# Sheet_V3.net
KiCad netlist of a schematic drawn in Altium Designer
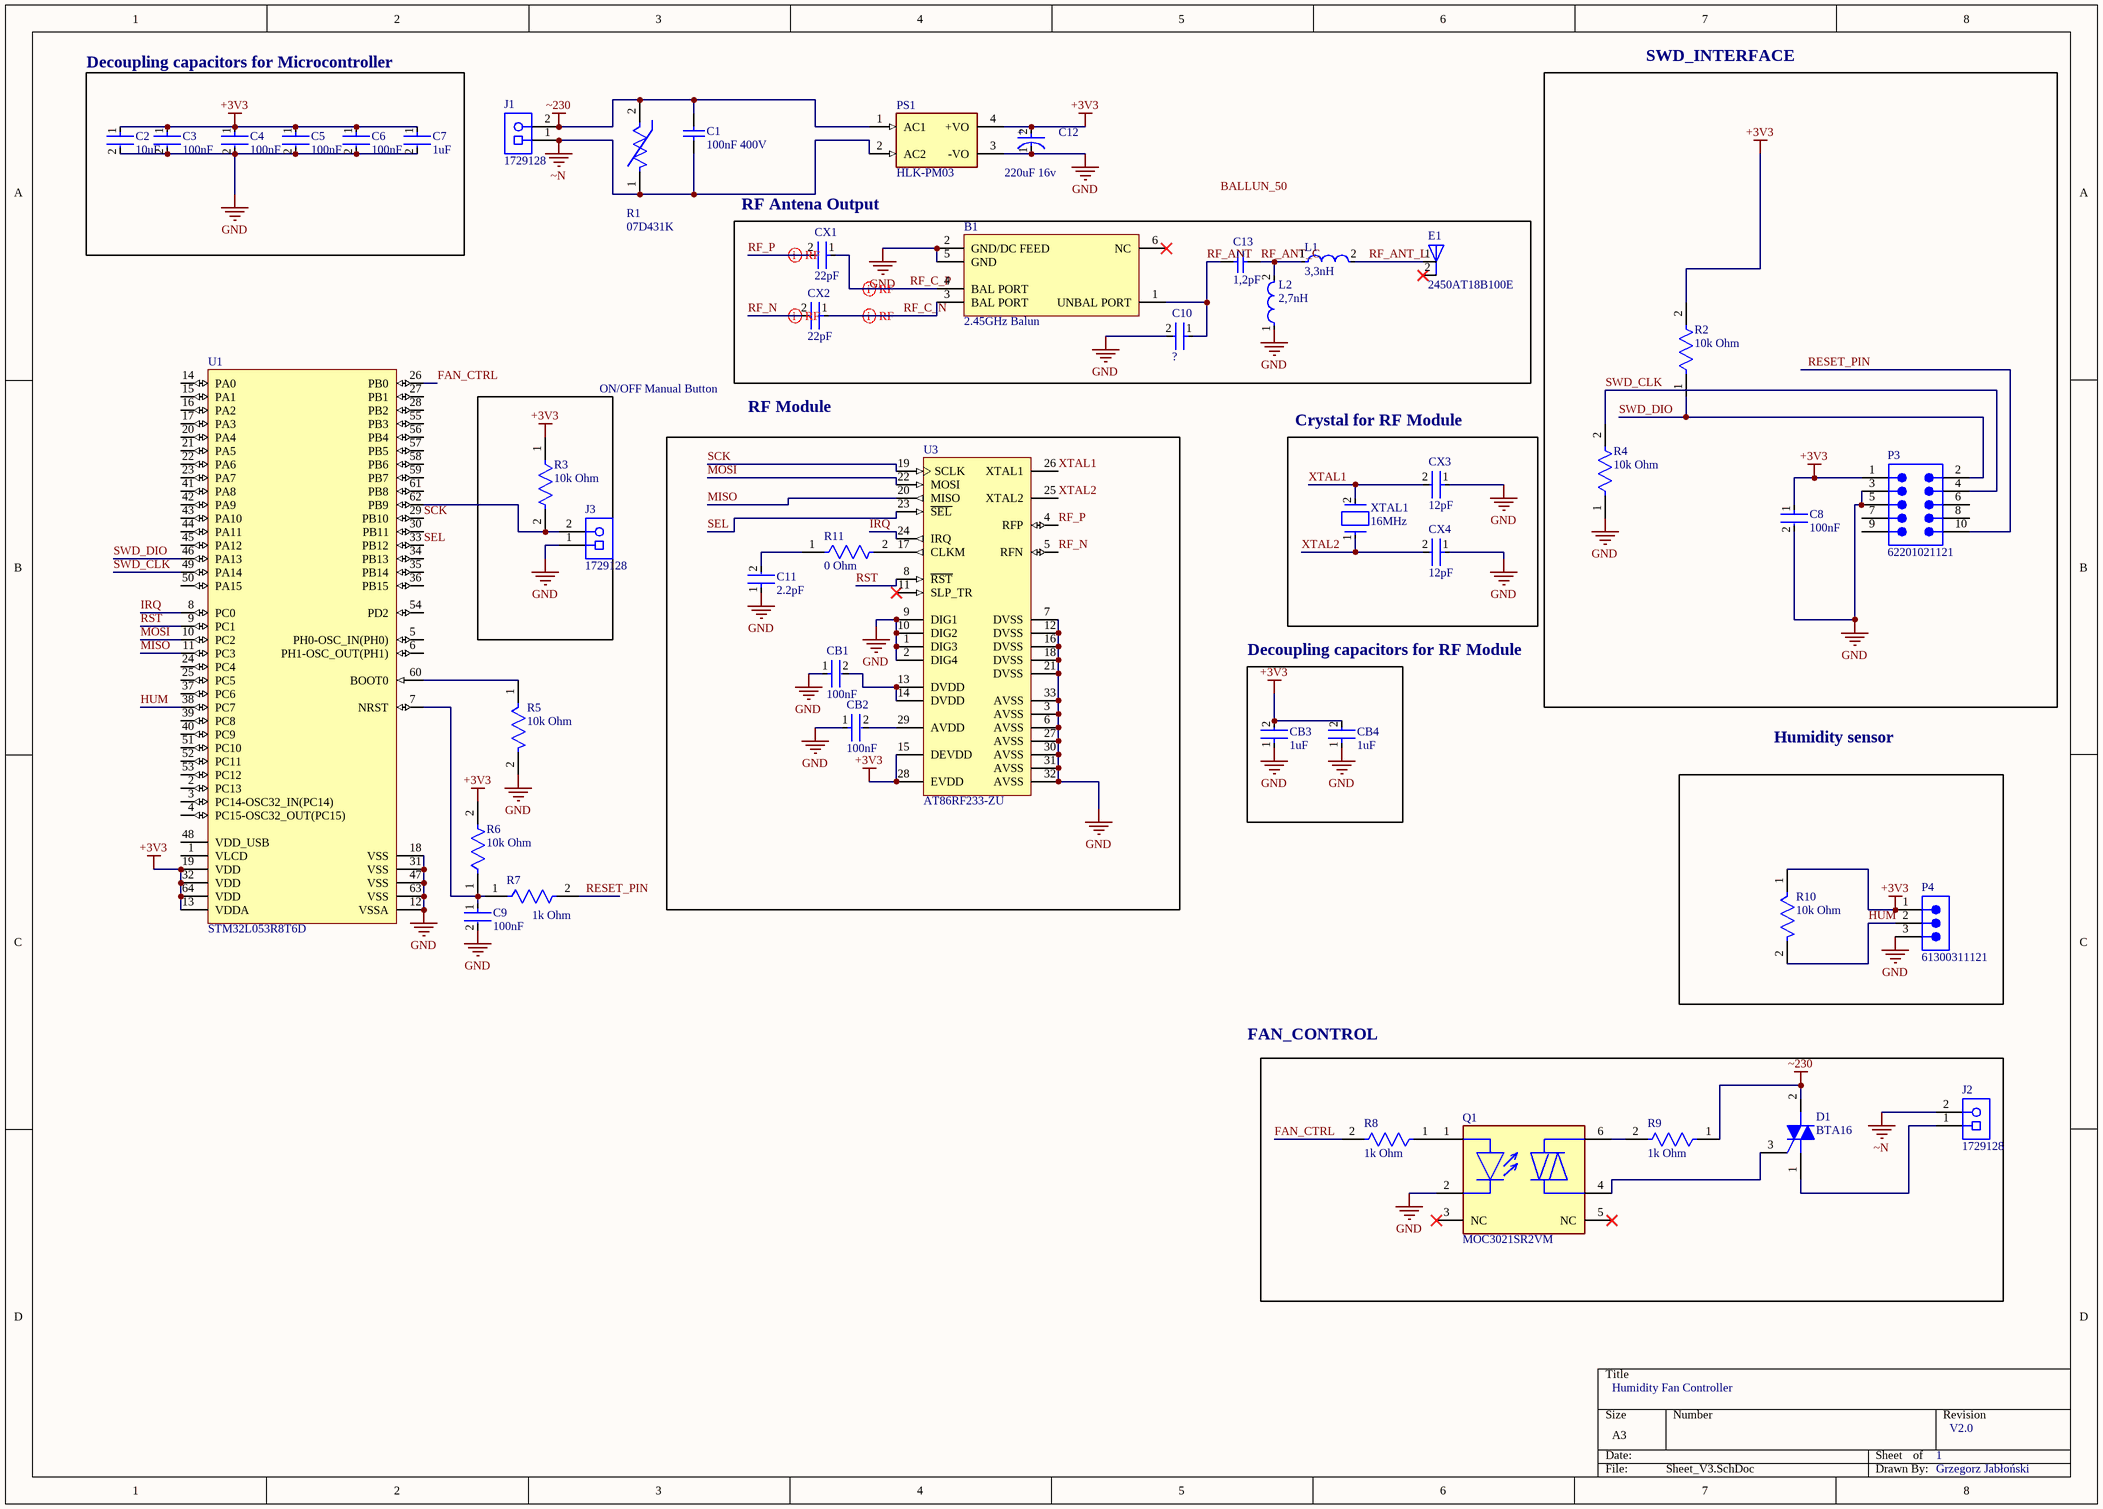
[diagram p0: Sheet_V3.SchDoc]

(export (version "E")
  (design (tool "Eeschema 10.0.6"))
  (components
    (comp (ref "B1")
      (value "2.45GHz Balun")
      (footprint "WE-BAL_0805")
      (description "748421245 100O Surface Mount Chip Balun")
      (libsource (lib "Altium Content Vault") (part "WE-BAL_0805"))
    )
    (comp (ref "C1")
      (value "100nF 400V")
      (footprint "TDK-B32921C3104M")
      (description "EMI Suppression Capacitor (MKP), 0.1 uF, +/- 20%, 305 V, 2-Pin THD, RoHS, Bulk")
      (fields (field (name "MANUFACTURER") "TDK") (field (name "TOLERANCE") "±20%"))
      (libsource (lib "Altium Content Vault") (part "CAP-NP-2"))
    )
    (comp (ref "C2")
      (value "10uF")
      (footprint "FP-CC0805-0_85-MFG")
      (description "CAP CER 0.1UF 50V X7R 0805")
      (fields (field (name "TOLERANCE") "0.1") (field (name "MANUFACTURER PART NUMBER") "CC0805KRX7R9BB104"))
      (libsource (lib "Altium Content Vault") (part "11868f565c42a9108669ba33697ecf6"))
    )
    (comp (ref "C3")
      (value "100nF")
      (footprint "FP-CC0805-0_85-MFG")
      (description "CAP CER 0.1UF 50V X7R 0805")
      (fields (field (name "TOLERANCE") "0.1") (field (name "MANUFACTURER PART NUMBER") "CC0805KRX7R9BB104"))
      (libsource (lib "Altium Content Vault") (part "11868f565c42a9108669ba33697ecf6"))
    )
    (comp (ref "C4")
      (value "100nF")
      (footprint "FP-CC0805-0_85-MFG")
      (description "CAP CER 0.1UF 50V X7R 0805")
      (fields (field (name "TOLERANCE") "0.1") (field (name "MANUFACTURER PART NUMBER") "CC0805KRX7R9BB104"))
      (libsource (lib "Altium Content Vault") (part "11868f565c42a9108669ba33697ecf6"))
    )
    (comp (ref "C5")
      (value "100nF")
      (footprint "FP-CC0805-0_85-MFG")
      (description "CAP CER 0.1UF 50V X7R 0805")
      (fields (field (name "TOLERANCE") "0.1") (field (name "MANUFACTURER PART NUMBER") "CC0805KRX7R9BB104"))
      (libsource (lib "Altium Content Vault") (part "11868f565c42a9108669ba33697ecf6"))
    )
    (comp (ref "C6")
      (value "100nF")
      (footprint "FP-CC0805-0_85-MFG")
      (description "CAP CER 0.1UF 50V X7R 0805")
      (fields (field (name "TOLERANCE") "0.1") (field (name "MANUFACTURER PART NUMBER") "CC0805KRX7R9BB104"))
      (libsource (lib "Altium Content Vault") (part "11868f565c42a9108669ba33697ecf6"))
    )
    (comp (ref "C7")
      (value "1uF")
      (footprint "FP-CC0805-0_85-MFG")
      (description "CAP CER 0.1UF 50V X7R 0805")
      (fields (field (name "TOLERANCE") "0.1") (field (name "MANUFACTURER PART NUMBER") "CC0805KRX7R9BB104"))
      (libsource (lib "Altium Content Vault") (part "11868f565c42a9108669ba33697ecf6"))
    )
    (comp (ref "C8")
      (value "100nF")
      (footprint "FP-CC0805-0_85-MFG")
      (description "CAP CER 0.1UF 50V X7R 0805")
      (fields (field (name "TOLERANCE") "0.1") (field (name "MANUFACTURER PART NUMBER") "CC0805KRX7R9BB104"))
      (libsource (lib "Altium Content Vault") (part "11868f565c42a9108669ba33697ecf6"))
    )
    (comp (ref "C9")
      (value "100nF")
      (footprint "FP-CC0805-0_85-MFG")
      (description "CAP CER 0.1UF 50V X7R 0805")
      (fields (field (name "TOLERANCE") "0.1") (field (name "MANUFACTURER PART NUMBER") "CC0805KRX7R9BB104"))
      (libsource (lib "Altium Content Vault") (part "11868f565c42a9108669ba33697ecf6"))
    )
    (comp (ref "C10")
      (value "?")
      (footprint "FP-CC0805-0_85-MFG")
      (description "CAP CER 0.1UF 50V X7R 0805")
      (fields (field (name "TOLERANCE") "0.1") (field (name "MANUFACTURER PART NUMBER") "CC0805KRX7R9BB104"))
      (libsource (lib "Altium Content Vault") (part "11868f565c42a9108669ba33697ecf6"))
    )
    (comp (ref "C11")
      (value "2.2pF")
      (footprint "FP-CC0805-0_85-MFG")
      (description "CAP CER 0.1UF 50V X7R 0805")
      (fields (field (name "TOLERANCE") "0.1") (field (name "MANUFACTURER PART NUMBER") "CC0805KRX7R9BB104"))
      (libsource (lib "Altium Content Vault") (part "11868f565c42a9108669ba33697ecf6"))
    )
    (comp (ref "C12")
      (value "220uF 16v")
      (footprint "FP-OS-CON-TH-E13-d_0_6-MFG")
      (description "Conductive Polymer Aluminum Solid Capacitors (OS-CON) 560uF ±20% 16V RADIAL TH 8x13mm")
      (fields (field (name "TOLERANCE") "20%"))
      (libsource (lib "Altium Content Vault") (part "a00bbbee19879c290e62620ae7e47b1"))
    )
    (comp (ref "C13")
      (value "1,2pF")
      (footprint "CAPC1005X56X25NL10T15")
      (fields
        (field (name "MANUFACTURER") "AVX Interconnect / Elco")
        (field (name "PART NUMBER") "04023C561KAT2A")
      )
      (libsource (lib "Altium Content Vault") (part "CAP"))
    )
    (comp (ref "CB1")
      (value "100nF")
      (footprint "FP-CC0805-0_85-MFG")
      (description "CAP CER 0.1UF 50V X7R 0805")
      (fields (field (name "TOLERANCE") "0.1") (field (name "MANUFACTURER PART NUMBER") "CC0805KRX7R9BB104"))
      (libsource (lib "Altium Content Vault") (part "11868f565c42a9108669ba33697ecf6"))
    )
    (comp (ref "CB2")
      (value "100nF")
      (footprint "FP-CC0805-0_85-MFG")
      (description "CAP CER 0.1UF 50V X7R 0805")
      (fields (field (name "TOLERANCE") "0.1") (field (name "MANUFACTURER PART NUMBER") "CC0805KRX7R9BB104"))
      (libsource (lib "Altium Content Vault") (part "11868f565c42a9108669ba33697ecf6"))
    )
    (comp (ref "CB3")
      (value "1uF")
      (footprint "FP-CC0805-0_85-MFG")
      (description "CAP CER 0.1UF 50V X7R 0805")
      (fields (field (name "TOLERANCE") "0.1") (field (name "MANUFACTURER PART NUMBER") "CC0805KRX7R9BB104"))
      (libsource (lib "Altium Content Vault") (part "11868f565c42a9108669ba33697ecf6"))
    )
    (comp (ref "CB4")
      (value "1uF")
      (footprint "FP-CC0805-0_85-MFG")
      (description "CAP CER 0.1UF 50V X7R 0805")
      (fields (field (name "TOLERANCE") "0.1") (field (name "MANUFACTURER PART NUMBER") "CC0805KRX7R9BB104"))
      (libsource (lib "Altium Content Vault") (part "11868f565c42a9108669ba33697ecf6"))
    )
    (comp (ref "CX1")
      (value "22pF")
      (footprint "FP-CC0805-0_85-MFG")
      (description "CAP CER 0.1UF 50V X7R 0805")
      (fields (field (name "TOLERANCE") "0.1") (field (name "MANUFACTURER PART NUMBER") "CC0805KRX7R9BB104"))
      (libsource (lib "Altium Content Vault") (part "11868f565c42a9108669ba33697ecf6"))
    )
    (comp (ref "CX2")
      (value "22pF")
      (footprint "FP-CC0805-0_85-MFG")
      (description "CAP CER 0.1UF 50V X7R 0805")
      (fields (field (name "TOLERANCE") "0.1") (field (name "MANUFACTURER PART NUMBER") "CC0805KRX7R9BB104"))
      (libsource (lib "Altium Content Vault") (part "11868f565c42a9108669ba33697ecf6"))
    )
    (comp (ref "CX3")
      (value "12pF")
      (footprint "FP-CC0805-0_85-MFG")
      (description "CAP CER 0.1UF 50V X7R 0805")
      (fields (field (name "TOLERANCE") "0.1") (field (name "MANUFACTURER PART NUMBER") "CC0805KRX7R9BB104"))
      (libsource (lib "Altium Content Vault") (part "11868f565c42a9108669ba33697ecf6"))
    )
    (comp (ref "CX4")
      (value "12pF")
      (footprint "FP-CC0805-0_85-MFG")
      (description "CAP CER 0.1UF 50V X7R 0805")
      (fields (field (name "TOLERANCE") "0.1") (field (name "MANUFACTURER PART NUMBER") "CC0805KRX7R9BB104"))
      (libsource (lib "Altium Content Vault") (part "11868f565c42a9108669ba33697ecf6"))
    )
    (comp (ref "D1")
      (value "BTA16")
      (footprint "ONSC-TO-220-3-221A-09")
      (description "Sensitive Gate Triacs, Silicon Bidirectional Thyristor, 3-Pin TO-220, Pb-Free, Bulk Box")
      (fields (field (name "PARTNUMBER") "MAC228A6G") (field (name "MANUFACTURER") "On Semiconductor"))
      (libsource (lib "Altium Content Vault") (part "ONSC-TRIAC-MT1MT2G-3"))
    )
    (comp (ref "E1")
      (value "2450AT18B100E")
      (footprint "XDCR_2450AT18B100E")
      (description "2.4GHz - Chip RF Antenna 2.4GHz ~ 2.5GHz 0.5dBi Solder Surface Mount")
      (fields (field (name "MF") "Johanson Technology"))
      (libsource (lib "2450AT18B100E") (part "2450AT18B100E"))
    )
    (comp (ref "J1")
      (value "1729128")
      (footprint "PHOE-1729128-2_V")
      (description "PCB Terminal Block, 13.5 A, 400 V, 2-Pin THD, RoHS, Bulk")
      (fields (field (name "MANUFACTURER") "Phoenix Contact"))
      (libsource (lib "") (part "CN-2P-F-R2_1"))
    )
    (comp (ref "J2")
      (value "1729128")
      (footprint "PHOE-1729128-2_V")
      (description "PCB Terminal Block, 13.5 A, 400 V, 2-Pin THD, RoHS, Bulk")
      (fields (field (name "MANUFACTURER") "Phoenix Contact"))
      (libsource (lib "Altium Content Vault") (part "CN-2P-F-R2"))
    )
    (comp (ref "J3")
      (value "1729128")
      (footprint "PHOE-1729128-2_V")
      (description "PCB Terminal Block, 13.5 A, 400 V, 2-Pin THD, RoHS, Bulk")
      (fields (field (name "MANUFACTURER") "Phoenix Contact"))
      (libsource (lib "Altium Content Vault") (part "CN-2P-F-R2"))
    )
    (comp (ref "L1")
      (value "3,3nH")
      (footprint "FP-L-07-MFG")
      (description "FIXED IND 3.3NH 300MA 190MOHM SM")
      (libsource (lib "Altium Content Vault") (part "725321dda6339637d4d059423bc1c3c"))
    )
    (comp (ref "L2")
      (value "2,7nH")
      (footprint "FP-L-07-MFG")
      (description "FIXED IND 3.3NH 300MA 190MOHM SM")
      (libsource (lib "Altium Content Vault") (part "725321dda6339637d4d059423bc1c3c"))
    )
    (comp (ref "P3")
      (value "62201021121")
      (footprint "62201021121")
      (libsource (lib "Altium Content Vault") (part "Header_Male_2R_10P"))
    )
    (comp (ref "P4")
      (value "61300311121")
      (footprint "61300311121")
      (libsource (lib "Altium Content Vault") (part "Header_Male_1R_03P"))
    )
    (comp (ref "PS1")
      (value "HLK-PM03")
      (footprint "CONV_HLK-PM03")
      (fields (field (name "MF") "Hi-link"))
      (libsource (lib "HLK-PM03") (part "HLK-PM03"))
    )
    (comp (ref "Q1")
      (value "MOC3021SR2VM")
      (footprint "FP-646BY-MFG")
      (description "MOC3021SR2VM Triac Driver Output Optocoupler, 6-Pin DIP 400V Random Phase")
      (libsource (lib "Altium Content Vault") (part "315d33d7a3de83856d3bd334bf87c2f"))
    )
    (comp (ref "R1")
      (value "07D431K")
      (footprint "FP-B72207S0110K101-MFG")
      (description "VARISTOR 18V 250A DISC 7MM")
      (fields
        (field (name "MANUFACTURER") "EPCOS")
        (field (name "MANUFACTURER PART NUMBER") "B72207S0110K101")
      )
      (libsource (lib "Altium Content Vault") (part "78a88060d5b7b043d6e48adc4284376"))
    )
    (comp (ref "R2")
      (value "10k Ohm")
      (footprint "FP-RMCF0805-MFG")
      (description "RES 0 OHM JUMPER 1/8W 0805")
      (libsource (lib "Altium Content Vault") (part "1029c3af85768c4190bb7ad29bc67b5"))
    )
    (comp (ref "R3")
      (value "10k Ohm")
      (footprint "FP-RMCF0805-MFG")
      (description "RES 0 OHM JUMPER 1/8W 0805")
      (libsource (lib "Altium Content Vault") (part "1029c3af85768c4190bb7ad29bc67b5"))
    )
    (comp (ref "R4")
      (value "10k Ohm")
      (footprint "FP-RMCF0805-MFG")
      (description "RES 0 OHM JUMPER 1/8W 0805")
      (libsource (lib "Altium Content Vault") (part "1029c3af85768c4190bb7ad29bc67b5"))
    )
    (comp (ref "R5")
      (value "10k Ohm")
      (footprint "FP-RMCF0805-MFG")
      (description "RES 0 OHM JUMPER 1/8W 0805")
      (libsource (lib "Altium Content Vault") (part "1029c3af85768c4190bb7ad29bc67b5"))
    )
    (comp (ref "R6")
      (value "10k Ohm")
      (footprint "FP-RMCF0805-MFG")
      (description "RES 0 OHM JUMPER 1/8W 0805")
      (libsource (lib "Altium Content Vault") (part "1029c3af85768c4190bb7ad29bc67b5"))
    )
    (comp (ref "R7")
      (value "1k Ohm")
      (footprint "FP-RMCF0805-MFG")
      (description "RES 0 OHM JUMPER 1/8W 0805")
      (libsource (lib "Altium Content Vault") (part "1029c3af85768c4190bb7ad29bc67b5"))
    )
    (comp (ref "R8")
      (value "1k Ohm")
      (footprint "FP-RMCF0805-MFG")
      (description "RES 0 OHM JUMPER 1/8W 0805")
      (libsource (lib "Altium Content Vault") (part "1029c3af85768c4190bb7ad29bc67b5"))
    )
    (comp (ref "R9")
      (value "1k Ohm")
      (footprint "FP-RMCF0805-MFG")
      (description "RES 0 OHM JUMPER 1/8W 0805")
      (libsource (lib "Altium Content Vault") (part "1029c3af85768c4190bb7ad29bc67b5"))
    )
    (comp (ref "R10")
      (value "10k Ohm")
      (footprint "FP-RMCF0805-MFG")
      (description "RES 0 OHM JUMPER 1/8W 0805")
      (libsource (lib "Altium Content Vault") (part "1029c3af85768c4190bb7ad29bc67b5"))
    )
    (comp (ref "R11")
      (value "0 Ohm")
      (footprint "FP-RMCF0805-MFG")
      (description "RES 0 OHM JUMPER 1/8W 0805")
      (libsource (lib "Altium Content Vault") (part "1029c3af85768c4190bb7ad29bc67b5"))
    )
    (comp (ref "U1")
      (value "STM32L053R8T6D")
      (footprint "STM-LQFP64_L")
      (libsource (lib "Altium Content Vault") (part "MC-ARM-STM32L053-LQFP64"))
    )
    (comp (ref "U3")
      (value "AT86RF233-ZU")
      (footprint "32QN2_M")
      (fields (field (name "MANUFACTURER") "Atmel"))
      (libsource (lib "Altium Content Vault") (part "ATML-AT86RF233-QN-32"))
    )
    (comp (ref "XTAL1")
      (value "16MHz")
      (footprint "FP-ABLS-MFG")
      (description "CRYSTAL 16.0000MHZ 18PF SMD")
      (fields
        (field (name "TOLERANCE") "30ppm")
        (field (name "MANUFACTURER PART NUMBER") "ABLS-16.000MHZ-K4T")
      )
      (libsource (lib "Altium Content Vault") (part "c23a69dc6c9e2f18f2079038eb95dd1"))
    )
  )
  (nets
    (net (code "1") (name "+3V3") (class "Default")
      (node (ref "C12") (pin "2") (pinfunction "A_2") (pintype "passive"))
      (node (ref "C2") (pin "1") (pinfunction "1_1") (pintype "passive"))
      (node (ref "C3") (pin "1") (pinfunction "1_1") (pintype "passive"))
      (node (ref "C4") (pin "1") (pinfunction "1_1") (pintype "passive"))
      (node (ref "C5") (pin "1") (pinfunction "1_1") (pintype "passive"))
      (node (ref "C6") (pin "1") (pinfunction "1_1") (pintype "passive"))
      (node (ref "C7") (pin "1") (pinfunction "1_1") (pintype "passive"))
      (node (ref "C8") (pin "1") (pinfunction "1_1") (pintype "passive"))
      (node (ref "CB3") (pin "2") (pinfunction "2_2") (pintype "passive"))
      (node (ref "CB4") (pin "2") (pinfunction "2_2") (pintype "passive"))
      (node (ref "P3") (pin "1") (pinfunction "1_1") (pintype "passive"))
      (node (ref "P4") (pin "1") (pinfunction "1_1") (pintype "passive"))
      (node (ref "PS1") (pin "4") (pinfunction "+VO_4") (pintype "power_in"))
      (node (ref "R10") (pin "1") (pinfunction "1_1") (pintype "passive"))
      (node (ref "R2") (pin "2") (pinfunction "2_2") (pintype "passive"))
      (node (ref "R3") (pin "1") (pinfunction "1_1") (pintype "passive"))
      (node (ref "R6") (pin "2") (pinfunction "2_2") (pintype "passive"))
      (node (ref "U1") (pin "13") (pinfunction "VDDA_13") (pintype "power_in"))
      (node (ref "U1") (pin "19") (pinfunction "VDD_19") (pintype "power_in"))
      (node (ref "U1") (pin "32") (pinfunction "VDD_32") (pintype "power_in"))
      (node (ref "U1") (pin "64") (pinfunction "VDD_64") (pintype "power_in"))
      (node (ref "U3") (pin "15") (pinfunction "DEVDD_15") (pintype "power_in"))
      (node (ref "U3") (pin "28") (pinfunction "EVDD_28") (pintype "power_in"))
    )
    (net (code "3") (name "/FAN_CTRL") (class "Default")
      (node (ref "R8") (pin "2") (pinfunction "2_2") (pintype "passive"))
      (node (ref "U1") (pin "26") (pinfunction "PB0_26") (pintype "bidirectional"))
    )
    (net (code "4") (name "/HUM") (class "Default")
      (node (ref "P4") (pin "2") (pinfunction "2_2") (pintype "passive"))
      (node (ref "R10") (pin "2") (pinfunction "2_2") (pintype "passive"))
      (node (ref "U1") (pin "38") (pinfunction "PC7_38") (pintype "bidirectional"))
    )
    (net (code "5") (name "/IRQ") (class "Default")
      (node (ref "U1") (pin "8") (pinfunction "PC0_8") (pintype "bidirectional"))
      (node (ref "U3") (pin "24") (pinfunction "IRQ_24") (pintype "output"))
    )
    (net (code "6") (name "/MISO") (class "Default")
      (node (ref "U1") (pin "11") (pinfunction "PC3_11") (pintype "bidirectional"))
      (node (ref "U3") (pin "20") (pinfunction "MISO_20") (pintype "output"))
    )
    (net (code "7") (name "/MOSI") (class "Default")
      (node (ref "U1") (pin "10") (pinfunction "PC2_10") (pintype "bidirectional"))
      (node (ref "U3") (pin "22") (pinfunction "MOSI_22") (pintype "input"))
    )
    (net (code "8") (name "/RESET_PIN") (class "Default")
      (node (ref "P3") (pin "10") (pinfunction "10_10") (pintype "passive"))
      (node (ref "R7") (pin "2") (pinfunction "2_2") (pintype "passive"))
    )
    (net (code "9") (name "/RF_ANT") (class "Default")
      (node (ref "B1") (pin "1") (pinfunction "UNBAL_PORT_1") (pintype "passive"))
      (node (ref "C10") (pin "1") (pinfunction "1_1") (pintype "passive"))
      (node (ref "C13") (pin "1") (pinfunction "1_1") (pintype "passive"))
    )
    (net (code "10") (name "/RF_ANT_C") (class "Default")
      (node (ref "C13") (pin "2") (pinfunction "2_2") (pintype "passive"))
      (node (ref "L1") (pin "1") (pinfunction "1_1") (pintype "passive"))
      (node (ref "L2") (pin "2") (pinfunction "2_2") (pintype "passive"))
    )
    (net (code "11") (name "/RF_ANT_L") (class "Default")
      (node (ref "E1") (pin "1") (pinfunction "FEED_1") (pintype "passive"))
      (node (ref "L1") (pin "2") (pinfunction "2_2") (pintype "passive"))
    )
    (net (code "12") (name "/RF_C_N") (class "Default")
      (node (ref "B1") (pin "3") (pinfunction "BAL_PORT_3") (pintype "passive"))
      (node (ref "CX2") (pin "1") (pinfunction "1_1") (pintype "passive"))
    )
    (net (code "13") (name "/RF_C_P") (class "Default")
      (node (ref "B1") (pin "4") (pinfunction "BAL_PORT_4") (pintype "passive"))
      (node (ref "CX1") (pin "1") (pinfunction "1_1") (pintype "passive"))
    )
    (net (code "14") (name "/RF_N") (class "Default")
      (node (ref "CX2") (pin "2") (pinfunction "2_2") (pintype "passive"))
      (node (ref "U3") (pin "5") (pinfunction "RFN_5") (pintype "bidirectional"))
    )
    (net (code "15") (name "/RF_P") (class "Default")
      (node (ref "CX1") (pin "2") (pinfunction "2_2") (pintype "passive"))
      (node (ref "U3") (pin "4") (pinfunction "RFP_4") (pintype "bidirectional"))
    )
    (net (code "16") (name "/RST") (class "Default")
      (node (ref "U1") (pin "9") (pinfunction "PC1_9") (pintype "bidirectional"))
      (node (ref "U3") (pin "8") (pinfunction "~{RST}_8") (pintype "input"))
    )
    (net (code "17") (name "/SCK") (class "Default")
      (node (ref "U1") (pin "29") (pinfunction "PB10_29") (pintype "bidirectional"))
      (node (ref "U3") (pin "19") (pinfunction "SCLK_19") (pintype "input"))
    )
    (net (code "18") (name "/SEL") (class "Default")
      (node (ref "U1") (pin "33") (pinfunction "PB12_33") (pintype "bidirectional"))
      (node (ref "U3") (pin "23") (pinfunction "~{SEL}_23") (pintype "input"))
    )
    (net (code "19") (name "/SWD_CLK") (class "Default")
      (node (ref "P3") (pin "4") (pinfunction "4_4") (pintype "passive"))
      (node (ref "R4") (pin "2") (pinfunction "2_2") (pintype "passive"))
      (node (ref "U1") (pin "49") (pinfunction "PA14_49") (pintype "bidirectional"))
    )
    (net (code "20") (name "/SWD_DIO") (class "Default")
      (node (ref "P3") (pin "2") (pinfunction "2_2") (pintype "passive"))
      (node (ref "R2") (pin "1") (pinfunction "1_1") (pintype "passive"))
      (node (ref "U1") (pin "46") (pinfunction "PA13_46") (pintype "bidirectional"))
    )
    (net (code "21") (name "/XTAL1") (class "Default")
      (node (ref "CX3") (pin "2") (pinfunction "2_2") (pintype "passive"))
      (node (ref "U3") (pin "26") (pinfunction "XTAL1_26") (pintype "passive"))
      (node (ref "XTAL1") (pin "2") (pinfunction "2_2") (pintype "passive"))
    )
    (net (code "22") (name "/XTAL2") (class "Default")
      (node (ref "CX4") (pin "2") (pinfunction "2_2") (pintype "passive"))
      (node (ref "U3") (pin "25") (pinfunction "XTAL2_25") (pintype "passive"))
      (node (ref "XTAL1") (pin "1") (pinfunction "1_1") (pintype "passive"))
    )
    (net (code "23") (name "GND") (class "Default")
      (node (ref "B1") (pin "2") (pinfunction "GND/DC_FEED_2") (pintype "power_in"))
      (node (ref "B1") (pin "5") (pinfunction "GND_5") (pintype "power_in"))
      (node (ref "C10") (pin "2") (pinfunction "2_2") (pintype "passive"))
      (node (ref "C11") (pin "1") (pinfunction "1_1") (pintype "passive"))
      (node (ref "C12") (pin "1") (pinfunction "C_1") (pintype "passive"))
      (node (ref "C2") (pin "2") (pinfunction "2_2") (pintype "passive"))
      (node (ref "C3") (pin "2") (pinfunction "2_2") (pintype "passive"))
      (node (ref "C4") (pin "2") (pinfunction "2_2") (pintype "passive"))
      (node (ref "C5") (pin "2") (pinfunction "2_2") (pintype "passive"))
      (node (ref "C6") (pin "2") (pinfunction "2_2") (pintype "passive"))
      (node (ref "C7") (pin "2") (pinfunction "2_2") (pintype "passive"))
      (node (ref "C8") (pin "2") (pinfunction "2_2") (pintype "passive"))
      (node (ref "C9") (pin "2") (pinfunction "2_2") (pintype "passive"))
      (node (ref "CB1") (pin "1") (pinfunction "1_1") (pintype "passive"))
      (node (ref "CB2") (pin "1") (pinfunction "1_1") (pintype "passive"))
      (node (ref "CB3") (pin "1") (pinfunction "1_1") (pintype "passive"))
      (node (ref "CB4") (pin "1") (pinfunction "1_1") (pintype "passive"))
      (node (ref "CX3") (pin "1") (pinfunction "1_1") (pintype "passive"))
      (node (ref "CX4") (pin "1") (pinfunction "1_1") (pintype "passive"))
      (node (ref "J3") (pin "1") (pinfunction "1_1") (pintype "passive"))
      (node (ref "L2") (pin "1") (pinfunction "1_1") (pintype "passive"))
      (node (ref "P3") (pin "3") (pinfunction "3_3") (pintype "passive"))
      (node (ref "P3") (pin "5") (pinfunction "5_5") (pintype "passive"))
      (node (ref "P4") (pin "3") (pinfunction "3_3") (pintype "passive"))
      (node (ref "PS1") (pin "3") (pinfunction "-VO_3") (pintype "power_in"))
      (node (ref "Q1") (pin "2") (pinfunction "C_2") (pintype "passive"))
      (node (ref "R4") (pin "1") (pinfunction "1_1") (pintype "passive"))
      (node (ref "R5") (pin "2") (pinfunction "2_2") (pintype "passive"))
      (node (ref "U1") (pin "12") (pinfunction "VSSA_12") (pintype "power_in"))
      (node (ref "U1") (pin "18") (pinfunction "VSS_18") (pintype "power_in"))
      (node (ref "U1") (pin "31") (pinfunction "VSS_31") (pintype "power_in"))
      (node (ref "U1") (pin "47") (pinfunction "VSS_47") (pintype "power_in"))
      (node (ref "U1") (pin "63") (pinfunction "VSS_63") (pintype "power_in"))
      (node (ref "U3") (pin "1") (pinfunction "DIG3_1") (pintype "passive"))
      (node (ref "U3") (pin "10") (pinfunction "DIG2_10") (pintype "passive"))
      (node (ref "U3") (pin "12") (pinfunction "DVSS_12") (pintype "power_in"))
      (node (ref "U3") (pin "16") (pinfunction "DVSS_16") (pintype "power_in"))
      (node (ref "U3") (pin "18") (pinfunction "DVSS_18") (pintype "power_in"))
      (node (ref "U3") (pin "2") (pinfunction "DIG4_2") (pintype "passive"))
      (node (ref "U3") (pin "21") (pinfunction "DVSS_21") (pintype "power_in"))
      (node (ref "U3") (pin "27") (pinfunction "AVSS_27") (pintype "power_in"))
      (node (ref "U3") (pin "3") (pinfunction "AVSS_3") (pintype "power_in"))
      (node (ref "U3") (pin "30") (pinfunction "AVSS_30") (pintype "power_in"))
      (node (ref "U3") (pin "31") (pinfunction "AVSS_31") (pintype "power_in"))
      (node (ref "U3") (pin "32") (pinfunction "AVSS_32") (pintype "power_in"))
      (node (ref "U3") (pin "33") (pinfunction "AVSS_33") (pintype "power_in"))
      (node (ref "U3") (pin "6") (pinfunction "AVSS_6") (pintype "power_in"))
      (node (ref "U3") (pin "7") (pinfunction "DVSS_7") (pintype "power_in"))
      (node (ref "U3") (pin "9") (pinfunction "DIG1_9") (pintype "passive"))
    )
    (net (code "24") (name "Net-(C11-Pad2)") (class "Default")
      (node (ref "C11") (pin "2") (pinfunction "2_2") (pintype "passive"))
      (node (ref "R11") (pin "1") (pinfunction "1_1") (pintype "passive"))
    )
    (net (code "25") (name "Net-(CB1-Pad2)") (class "Default")
      (node (ref "CB1") (pin "2") (pinfunction "2_2") (pintype "passive"))
      (node (ref "U3") (pin "13") (pinfunction "DVDD_13") (pintype "power_in"))
      (node (ref "U3") (pin "14") (pinfunction "DVDD_14") (pintype "power_in"))
    )
    (net (code "26") (name "Net-(D1-G)") (class "Default")
      (node (ref "D1") (pin "3") (pinfunction "G_3") (pintype "passive"))
      (node (ref "Q1") (pin "4") (pinfunction "1_MAIN_TERM_4") (pintype "passive"))
    )
    (net (code "27") (name "Net-(D1-MT1)") (class "Default")
      (node (ref "D1") (pin "1") (pinfunction "MT1_1") (pintype "passive"))
      (node (ref "J2") (pin "1") (pinfunction "1_1") (pintype "passive"))
    )
    (net (code "28") (name "Net-(Q1-2_MAIN_TERM)") (class "Default")
      (node (ref "Q1") (pin "6") (pinfunction "2_MAIN_TERM_6") (pintype "passive"))
      (node (ref "R9") (pin "2") (pinfunction "2_2") (pintype "passive"))
    )
    (net (code "29") (name "Net-(Q1-A)") (class "Default")
      (node (ref "Q1") (pin "1") (pinfunction "A_1") (pintype "passive"))
      (node (ref "R8") (pin "1") (pinfunction "1_1") (pintype "passive"))
    )
    (net (code "30") (name "Net-(U1-BOOT0)") (class "Default")
      (node (ref "R5") (pin "1") (pinfunction "1_1") (pintype "passive"))
      (node (ref "U1") (pin "60") (pinfunction "BOOT0_60") (pintype "input"))
    )
    (net (code "31") (name "Net-(U1-NRST)") (class "Default")
      (node (ref "C9") (pin "1") (pinfunction "1_1") (pintype "passive"))
      (node (ref "R6") (pin "1") (pinfunction "1_1") (pintype "passive"))
      (node (ref "R7") (pin "1") (pinfunction "1_1") (pintype "passive"))
      (node (ref "U1") (pin "7") (pinfunction "NRST_7") (pintype "bidirectional"))
    )
    (net (code "32") (name "Net-(U1-PB9)") (class "Default")
      (node (ref "J3") (pin "2") (pinfunction "2_2") (pintype "passive"))
      (node (ref "R3") (pin "2") (pinfunction "2_2") (pintype "passive"))
      (node (ref "U1") (pin "62") (pinfunction "PB9_62") (pintype "bidirectional"))
    )
    (net (code "33") (name "Net-(U3-AVDD)") (class "Default")
      (node (ref "CB2") (pin "2") (pinfunction "2_2") (pintype "passive"))
      (node (ref "U3") (pin "29") (pinfunction "AVDD_29") (pintype "power_in"))
    )
    (net (code "34") (name "Net-(U3-CLKM)") (class "Default")
      (node (ref "R11") (pin "2") (pinfunction "2_2") (pintype "passive"))
      (node (ref "U3") (pin "17") (pinfunction "CLKM_17") (pintype "output"))
    )
    (net (code "35") (name "unconnected-(B1-NC-Pad6)") (class "Default")
      (node (ref "B1") (pin "6") (pinfunction "NC_6") (pintype "passive+no_connect"))
    )
    (net (code "36") (name "unconnected-(E1-NC-Pad2)") (class "Default")
      (node (ref "E1") (pin "2") (pinfunction "NC_2") (pintype "passive+no_connect"))
    )
    (net (code "37") (name "unconnected-(P3-Pad6)") (class "Default")
      (node (ref "P3") (pin "6") (pinfunction "6_6") (pintype "passive"))
    )
    (net (code "38") (name "unconnected-(P3-Pad7)") (class "Default")
      (node (ref "P3") (pin "7") (pinfunction "7_7") (pintype "passive"))
    )
    (net (code "39") (name "unconnected-(P3-Pad8)") (class "Default")
      (node (ref "P3") (pin "8") (pinfunction "8_8") (pintype "passive"))
    )
    (net (code "40") (name "unconnected-(P3-Pad9)") (class "Default")
      (node (ref "P3") (pin "9") (pinfunction "9_9") (pintype "passive"))
    )
    (net (code "41") (name "unconnected-(Q1-NC-Pad3)") (class "Default")
      (node (ref "Q1") (pin "3") (pinfunction "NC_3") (pintype "passive+no_connect"))
    )
    (net (code "42") (name "unconnected-(Q1-NC-Pad5)") (class "Default")
      (node (ref "Q1") (pin "5") (pinfunction "NC_5") (pintype "passive+no_connect"))
    )
    (net (code "43") (name "unconnected-(U1-PA0-Pad14)") (class "Default")
      (node (ref "U1") (pin "14") (pinfunction "PA0_14") (pintype "bidirectional"))
    )
    (net (code "44") (name "unconnected-(U1-PA1-Pad15)") (class "Default")
      (node (ref "U1") (pin "15") (pinfunction "PA1_15") (pintype "bidirectional"))
    )
    (net (code "45") (name "unconnected-(U1-PA2-Pad16)") (class "Default")
      (node (ref "U1") (pin "16") (pinfunction "PA2_16") (pintype "bidirectional"))
    )
    (net (code "46") (name "unconnected-(U1-PA3-Pad17)") (class "Default")
      (node (ref "U1") (pin "17") (pinfunction "PA3_17") (pintype "bidirectional"))
    )
    (net (code "47") (name "unconnected-(U1-PA4-Pad20)") (class "Default")
      (node (ref "U1") (pin "20") (pinfunction "PA4_20") (pintype "bidirectional"))
    )
    (net (code "48") (name "unconnected-(U1-PA5-Pad21)") (class "Default")
      (node (ref "U1") (pin "21") (pinfunction "PA5_21") (pintype "bidirectional"))
    )
    (net (code "49") (name "unconnected-(U1-PA6-Pad22)") (class "Default")
      (node (ref "U1") (pin "22") (pinfunction "PA6_22") (pintype "bidirectional"))
    )
    (net (code "50") (name "unconnected-(U1-PA7-Pad23)") (class "Default")
      (node (ref "U1") (pin "23") (pinfunction "PA7_23") (pintype "bidirectional"))
    )
    (net (code "51") (name "unconnected-(U1-PA8-Pad41)") (class "Default")
      (node (ref "U1") (pin "41") (pinfunction "PA8_41") (pintype "bidirectional"))
    )
    (net (code "52") (name "unconnected-(U1-PA9-Pad42)") (class "Default")
      (node (ref "U1") (pin "42") (pinfunction "PA9_42") (pintype "bidirectional"))
    )
    (net (code "53") (name "unconnected-(U1-PA10-Pad43)") (class "Default")
      (node (ref "U1") (pin "43") (pinfunction "PA10_43") (pintype "bidirectional"))
    )
    (net (code "54") (name "unconnected-(U1-PA11-Pad44)") (class "Default")
      (node (ref "U1") (pin "44") (pinfunction "PA11_44") (pintype "bidirectional"))
    )
    (net (code "55") (name "unconnected-(U1-PA12-Pad45)") (class "Default")
      (node (ref "U1") (pin "45") (pinfunction "PA12_45") (pintype "bidirectional"))
    )
    (net (code "56") (name "unconnected-(U1-PA15-Pad50)") (class "Default")
      (node (ref "U1") (pin "50") (pinfunction "PA15_50") (pintype "bidirectional"))
    )
    (net (code "57") (name "unconnected-(U1-PB1-Pad27)") (class "Default")
      (node (ref "U1") (pin "27") (pinfunction "PB1_27") (pintype "bidirectional"))
    )
    (net (code "58") (name "unconnected-(U1-PB2-Pad28)") (class "Default")
      (node (ref "U1") (pin "28") (pinfunction "PB2_28") (pintype "bidirectional"))
    )
    (net (code "59") (name "unconnected-(U1-PB3-Pad55)") (class "Default")
      (node (ref "U1") (pin "55") (pinfunction "PB3_55") (pintype "bidirectional"))
    )
    (net (code "60") (name "unconnected-(U1-PB4-Pad56)") (class "Default")
      (node (ref "U1") (pin "56") (pinfunction "PB4_56") (pintype "bidirectional"))
    )
    (net (code "61") (name "unconnected-(U1-PB5-Pad57)") (class "Default")
      (node (ref "U1") (pin "57") (pinfunction "PB5_57") (pintype "bidirectional"))
    )
    (net (code "62") (name "unconnected-(U1-PB6-Pad58)") (class "Default")
      (node (ref "U1") (pin "58") (pinfunction "PB6_58") (pintype "bidirectional"))
    )
    (net (code "63") (name "unconnected-(U1-PB7-Pad59)") (class "Default")
      (node (ref "U1") (pin "59") (pinfunction "PB7_59") (pintype "bidirectional"))
    )
    (net (code "64") (name "unconnected-(U1-PB8-Pad61)") (class "Default")
      (node (ref "U1") (pin "61") (pinfunction "PB8_61") (pintype "bidirectional"))
    )
    (net (code "65") (name "unconnected-(U1-PB11-Pad30)") (class "Default")
      (node (ref "U1") (pin "30") (pinfunction "PB11_30") (pintype "bidirectional"))
    )
    (net (code "66") (name "unconnected-(U1-PB13-Pad34)") (class "Default")
      (node (ref "U1") (pin "34") (pinfunction "PB13_34") (pintype "bidirectional"))
    )
    (net (code "67") (name "unconnected-(U1-PB14-Pad35)") (class "Default")
      (node (ref "U1") (pin "35") (pinfunction "PB14_35") (pintype "bidirectional"))
    )
    (net (code "68") (name "unconnected-(U1-PB15-Pad36)") (class "Default")
      (node (ref "U1") (pin "36") (pinfunction "PB15_36") (pintype "bidirectional"))
    )
    (net (code "69") (name "unconnected-(U1-PC4-Pad24)") (class "Default")
      (node (ref "U1") (pin "24") (pinfunction "PC4_24") (pintype "bidirectional"))
    )
    (net (code "70") (name "unconnected-(U1-PC5-Pad25)") (class "Default")
      (node (ref "U1") (pin "25") (pinfunction "PC5_25") (pintype "bidirectional"))
    )
    (net (code "71") (name "unconnected-(U1-PC6-Pad37)") (class "Default")
      (node (ref "U1") (pin "37") (pinfunction "PC6_37") (pintype "bidirectional"))
    )
    (net (code "72") (name "unconnected-(U1-PC8-Pad39)") (class "Default")
      (node (ref "U1") (pin "39") (pinfunction "PC8_39") (pintype "bidirectional"))
    )
    (net (code "73") (name "unconnected-(U1-PC9-Pad40)") (class "Default")
      (node (ref "U1") (pin "40") (pinfunction "PC9_40") (pintype "bidirectional"))
    )
    (net (code "74") (name "unconnected-(U1-PC10-Pad51)") (class "Default")
      (node (ref "U1") (pin "51") (pinfunction "PC10_51") (pintype "bidirectional"))
    )
    (net (code "75") (name "unconnected-(U1-PC11-Pad52)") (class "Default")
      (node (ref "U1") (pin "52") (pinfunction "PC11_52") (pintype "bidirectional"))
    )
    (net (code "76") (name "unconnected-(U1-PC12-Pad53)") (class "Default")
      (node (ref "U1") (pin "53") (pinfunction "PC12_53") (pintype "bidirectional"))
    )
    (net (code "77") (name "unconnected-(U1-PC13-Pad2)") (class "Default")
      (node (ref "U1") (pin "2") (pinfunction "PC13_2") (pintype "bidirectional"))
    )
    (net (code "78") (name "unconnected-(U1-PC14-OSC32_IN(PC14)-Pad3)") (class "Default")
      (node (ref "U1") (pin "3") (pinfunction "PC14-OSC32_IN(PC14)_3") (pintype "bidirectional"))
    )
    (net (code "79") (name "unconnected-(U1-PC15-OSC32_OUT(PC15)-Pad4)") (class "Default")
      (node (ref "U1") (pin "4") (pinfunction "PC15-OSC32_OUT(PC15)_4") (pintype "bidirectional"))
    )
    (net (code "80") (name "unconnected-(U1-PD2-Pad54)") (class "Default")
      (node (ref "U1") (pin "54") (pinfunction "PD2_54") (pintype "bidirectional"))
    )
    (net (code "81") (name "unconnected-(U1-PH0-OSC_IN(PH0)-Pad5)") (class "Default")
      (node (ref "U1") (pin "5") (pinfunction "PH0-OSC_IN(PH0)_5") (pintype "bidirectional"))
    )
    (net (code "82") (name "unconnected-(U1-PH1-OSC_OUT(PH1)-Pad6)") (class "Default")
      (node (ref "U1") (pin "6") (pinfunction "PH1-OSC_OUT(PH1)_6") (pintype "bidirectional"))
    )
    (net (code "83") (name "unconnected-(U1-VDD_USB-Pad48)") (class "Default")
      (node (ref "U1") (pin "48") (pinfunction "VDD_USB_48") (pintype "power_in"))
    )
    (net (code "84") (name "unconnected-(U1-VLCD-Pad1)") (class "Default")
      (node (ref "U1") (pin "1") (pinfunction "VLCD_1") (pintype "power_in"))
    )
    (net (code "85") (name "unconnected-(U3-SLP_TR-Pad11)") (class "Default")
      (node (ref "U3") (pin "11") (pinfunction "SLP_TR_11") (pintype "input+no_connect"))
    )
    (net (code "86") (name "~230") (class "Default")
      (node (ref "C1") (pin "2") (pinfunction "2_2") (pintype "passive"))
      (node (ref "D1") (pin "2") (pinfunction "MT2_2") (pintype "passive"))
      (node (ref "J1") (pin "2") (pinfunction "2_2") (pintype "passive"))
      (node (ref "PS1") (pin "1") (pinfunction "AC1_1") (pintype "input"))
      (node (ref "R1") (pin "2") (pinfunction "2_2") (pintype "passive"))
      (node (ref "R9") (pin "1") (pinfunction "1_1") (pintype "passive"))
    )
    (net (code "87") (name "~N") (class "Default")
      (node (ref "C1") (pin "1") (pinfunction "1_1") (pintype "passive"))
      (node (ref "J1") (pin "1") (pinfunction "1_1") (pintype "passive"))
      (node (ref "J2") (pin "2") (pinfunction "2_2") (pintype "passive"))
      (node (ref "PS1") (pin "2") (pinfunction "AC2_2") (pintype "input"))
      (node (ref "R1") (pin "1") (pinfunction "1_1") (pintype "passive"))
    )
  )
)
